# Nuio_Left_Keyboard_Rev_H_UI.net
KiCad netlist of a schematic drawn in Altium Designer
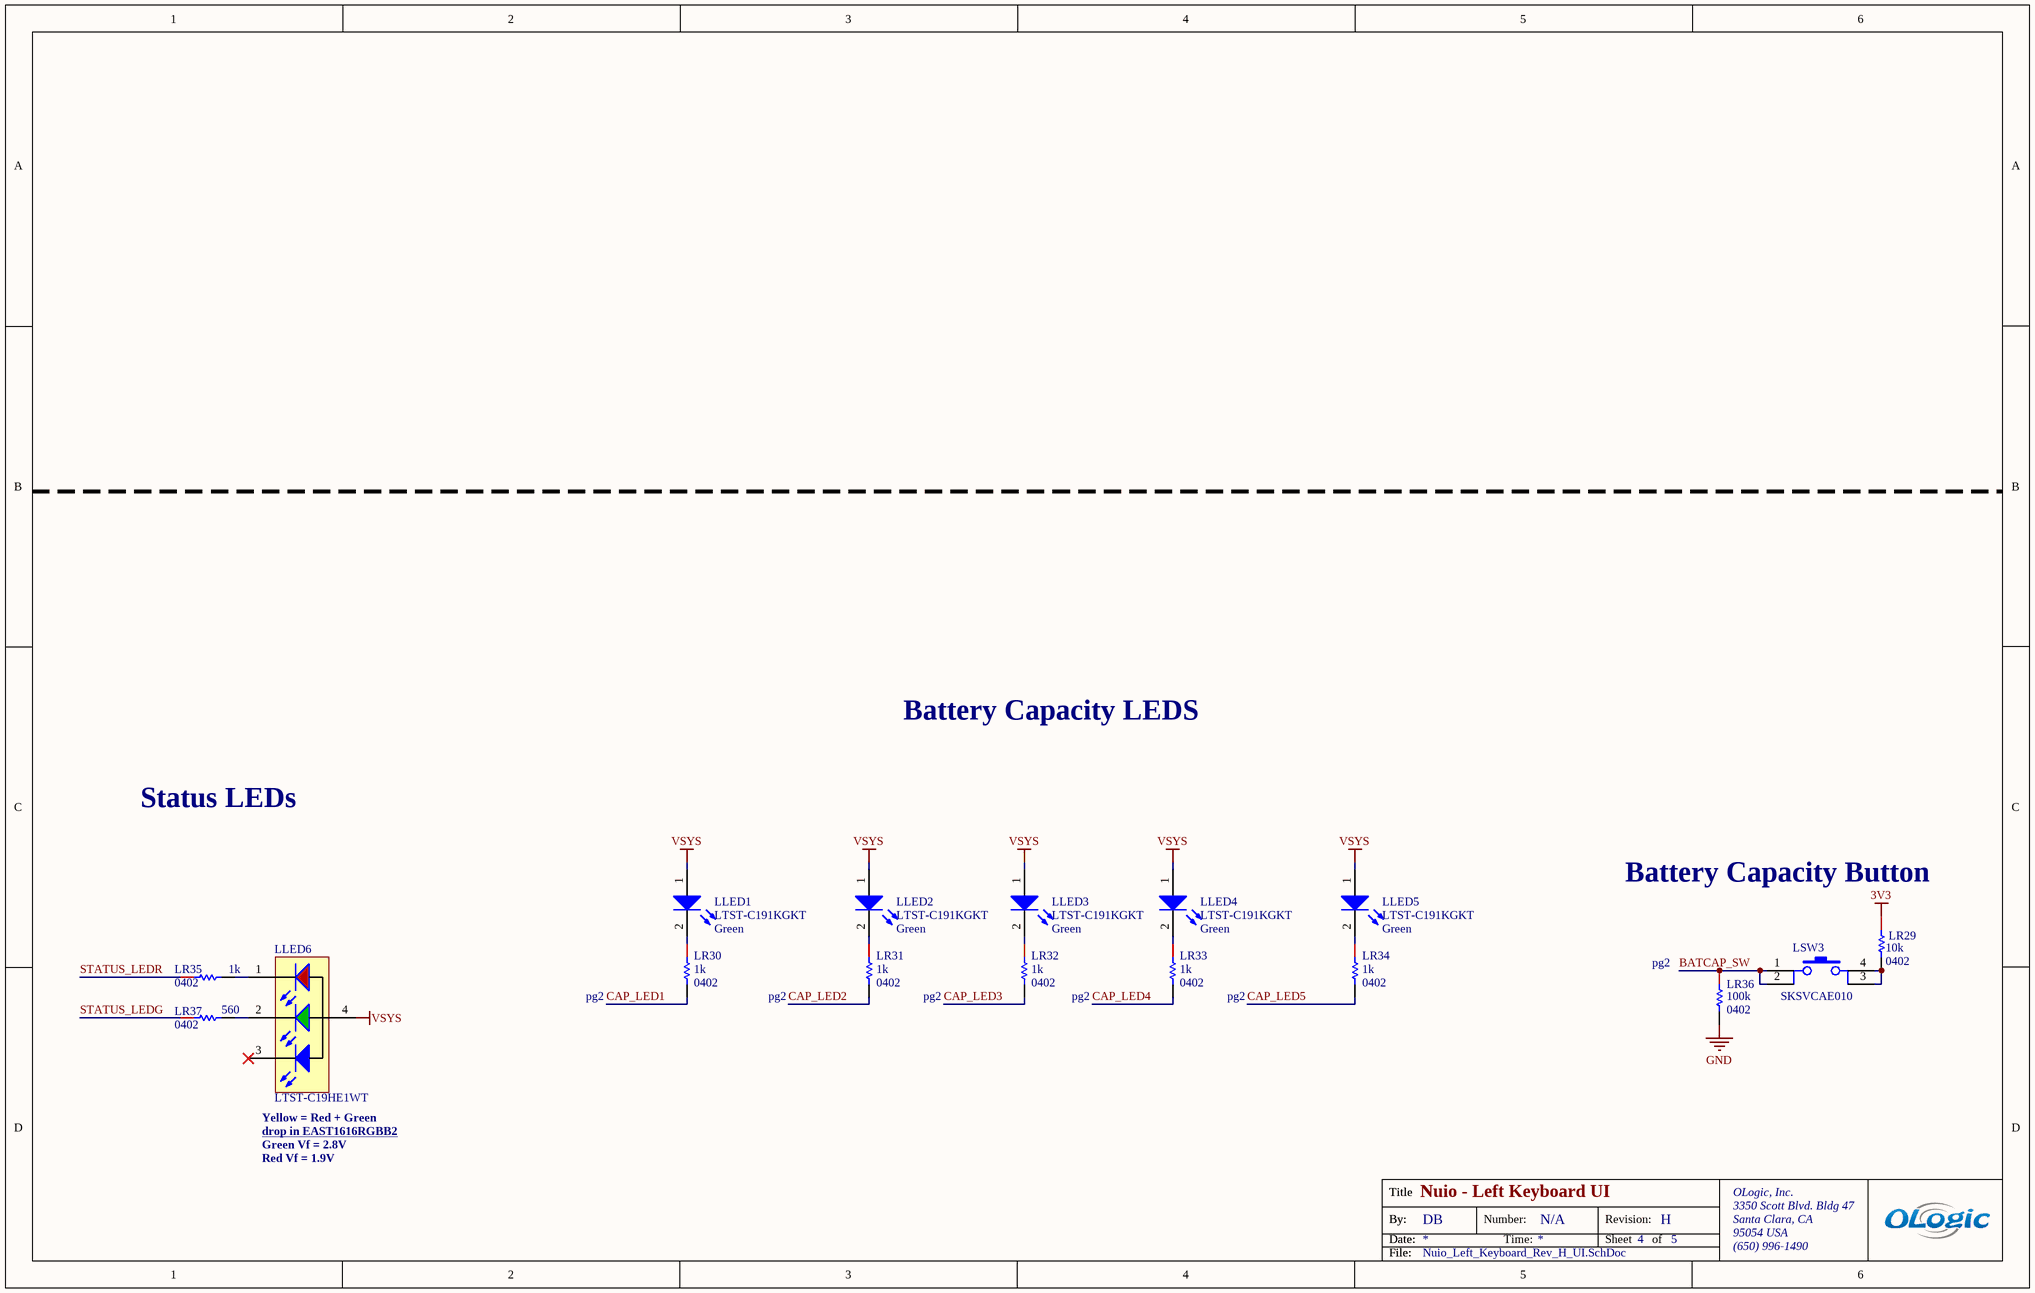
[diagram p0: Nuio_Left_Keyboard_Rev_H_UI.SchDoc]

(export (version "E")
  (design (tool "Eeschema 10.0.6"))
  (components
    (comp (ref "LLED1")
      (value "LTST-C191KGKT")
      (footprint "SM-LED-0603")
      (description "LED GREEN CLEAR THIN 0603 SMD")
      (fields
        (field (name "MANUFACTURER PART NUMBER") "LTST-C191KGKT")
        (field (name "COLOR") "Green")
        (field (name "MANUFACTURER") "Lite-On Inc")
      )
      (libsource (lib "OLogic Nexus Vault") (part "OL_LED"))
    )
    (comp (ref "LLED2")
      (value "LTST-C191KGKT")
      (footprint "SM-LED-0603")
      (description "LED GREEN CLEAR THIN 0603 SMD")
      (fields
        (field (name "MANUFACTURER PART NUMBER") "LTST-C191KGKT")
        (field (name "COLOR") "Green")
        (field (name "MANUFACTURER") "Lite-On Inc")
      )
      (libsource (lib "OLogic Nexus Vault") (part "OL_LED"))
    )
    (comp (ref "LLED3")
      (value "LTST-C191KGKT")
      (footprint "SM-LED-0603")
      (description "LED GREEN CLEAR THIN 0603 SMD")
      (fields
        (field (name "MANUFACTURER PART NUMBER") "LTST-C191KGKT")
        (field (name "COLOR") "Green")
        (field (name "MANUFACTURER") "Lite-On Inc")
      )
      (libsource (lib "OLogic Nexus Vault") (part "OL_LED"))
    )
    (comp (ref "LLED4")
      (value "LTST-C191KGKT")
      (footprint "SM-LED-0603")
      (description "LED GREEN CLEAR THIN 0603 SMD")
      (fields
        (field (name "MANUFACTURER PART NUMBER") "LTST-C191KGKT")
        (field (name "COLOR") "Green")
        (field (name "MANUFACTURER") "Lite-On Inc")
      )
      (libsource (lib "OLogic Nexus Vault") (part "OL_LED"))
    )
    (comp (ref "LLED5")
      (value "LTST-C191KGKT")
      (footprint "SM-LED-0603")
      (description "LED GREEN CLEAR THIN 0603 SMD")
      (fields
        (field (name "MANUFACTURER PART NUMBER") "LTST-C191KGKT")
        (field (name "COLOR") "Green")
        (field (name "MANUFACTURER") "Lite-On Inc")
      )
      (libsource (lib "OLogic Nexus Vault") (part "OL_LED"))
    )
    (comp (ref "LLED6")
      (value "LTST-C19HE1WT")
      (footprint "LTST-C19HE1WT")
      (description "LED RGB 605/525/470NM DIFF SMD")
      (fields (field (name "MANUFACTURER") "Lite-On Inc."))
      (libsource (lib "OLogic Nexus Vault") (part "LTST-C19HE1WT"))
    )
    (comp (ref "LR29")
      (value "RES SMD 10K OHM 1% 1/16W 0402")
      (footprint "RESC0402_YAGEO")
      (fields
        (field (name "RESISTANCE") "10k")
        (field (name "PACKAGE (IMPERIAL)") "0402")
        (field (name "MANUFACTURER") "Yageo")
        (field (name "TOLERANCE") "1%")
        (field (name "MANUFACTURER PART NUMBER") "AT0402FRE0710KL")
      )
      (libsource (lib "OLogic Nexus Vault") (part "OL_Resistor"))
    )
    (comp (ref "LR30")
      (value "RES SMD 1K OHM 1% 1/16W 0402")
      (footprint "RESC0402(1005)_L")
      (fields
        (field (name "RESISTANCE") "1k")
        (field (name "PACKAGE (IMPERIAL)") "0402")
        (field (name "POWER") "63mW")
        (field (name "MANUFACTURER") "Yageo")
        (field (name "TOLERANCE") "1%")
      )
      (libsource (lib "OLogic Nexus Vault") (part "OL_Resistor"))
    )
    (comp (ref "LR31")
      (value "RES SMD 1K OHM 1% 1/16W 0402")
      (footprint "RESC0402(1005)_L")
      (fields
        (field (name "RESISTANCE") "1k")
        (field (name "PACKAGE (IMPERIAL)") "0402")
        (field (name "POWER") "63mW")
        (field (name "MANUFACTURER") "Yageo")
        (field (name "TOLERANCE") "1%")
      )
      (libsource (lib "OLogic Nexus Vault") (part "OL_Resistor"))
    )
    (comp (ref "LR32")
      (value "RES SMD 1K OHM 1% 1/16W 0402")
      (footprint "RESC0402(1005)_L")
      (fields
        (field (name "RESISTANCE") "1k")
        (field (name "PACKAGE (IMPERIAL)") "0402")
        (field (name "POWER") "63mW")
        (field (name "MANUFACTURER") "Yageo")
        (field (name "TOLERANCE") "1%")
      )
      (libsource (lib "OLogic Nexus Vault") (part "OL_Resistor"))
    )
    (comp (ref "LR33")
      (value "RES SMD 1K OHM 1% 1/16W 0402")
      (footprint "RESC0402(1005)_L")
      (fields
        (field (name "RESISTANCE") "1k")
        (field (name "PACKAGE (IMPERIAL)") "0402")
        (field (name "POWER") "63mW")
        (field (name "MANUFACTURER") "Yageo")
        (field (name "TOLERANCE") "1%")
      )
      (libsource (lib "OLogic Nexus Vault") (part "OL_Resistor"))
    )
    (comp (ref "LR34")
      (value "RES SMD 1K OHM 1% 1/16W 0402")
      (footprint "RESC0402(1005)_L")
      (fields
        (field (name "RESISTANCE") "1k")
        (field (name "PACKAGE (IMPERIAL)") "0402")
        (field (name "POWER") "63mW")
        (field (name "MANUFACTURER") "Yageo")
        (field (name "TOLERANCE") "1%")
      )
      (libsource (lib "OLogic Nexus Vault") (part "OL_Resistor"))
    )
    (comp (ref "LR35")
      (value "RES SMD 1K OHM 1% 1/16W 0402")
      (footprint "RESC0402(1005)_L")
      (fields
        (field (name "RESISTANCE") "1k")
        (field (name "PACKAGE (IMPERIAL)") "0402")
        (field (name "POWER") "63mW")
        (field (name "MANUFACTURER") "Yageo")
        (field (name "TOLERANCE") "1%")
      )
      (libsource (lib "OLogic Nexus Vault") (part "OL_Resistor"))
    )
    (comp (ref "LR36")
      (value "100k")
      (footprint "RESC0402(1005)_L")
      (description "±1% 0.063W, 1/16W Chip Resistor 0402 (1005 Metric) Moisture Resistant Thick Film")
      (fields
        (field (name "CASE CODE (IMPERIAL)") "0402")
        (field (name "TOLERANCE") "1%")
        (field (name "MANUFACTURER") "YAGEO")
      )
      (libsource (lib "OLogic Nexus Vault") (part "=Resistance"))
    )
    (comp (ref "LR37")
      (value "560")
      (footprint "RESC0402(1005)_L")
      (description "RES SMD 560 OHM 1% 1/16W 0402")
      (fields
        (field (name "PACKAGE (IMPERIAL)") "0402")
        (field (name "POWER") "63mW")
        (field (name "RESISTANCE") "560")
        (field (name "TOLERANCE") "1%")
      )
      (libsource (lib "OLogic Nexus Vault") (part "=Resistance"))
    )
    (comp (ref "LSW3")
      (value "SKSVCAE010")
      (footprint "SKSVCAE010")
      (description "2.8x1.9mm Compact Type with Projection Surface Mount SKSV Series Tact Switch")
      (fields (field (name "MANUFACTURER") "Alps Alpine"))
      (libsource (lib "OLogic Nexus Vault") (part "OL_Switch_Tactile_4"))
    )
  )
  (nets
    (net (code "1") (name "/BATCAP_SW") (class "Default")
      (node (ref "LR36") (pin "1") (pinfunction "1_1") (pintype "passive"))
      (node (ref "LSW3") (pin "1") (pinfunction "1_1") (pintype "passive"))
      (node (ref "LSW3") (pin "2") (pinfunction "2_2") (pintype "passive"))
    )
    (net (code "2") (name "/CAP_LED1") (class "Default")
      (node (ref "LR30") (pin "2") (pinfunction "2_2") (pintype "passive"))
    )
    (net (code "3") (name "/CAP_LED2") (class "Default")
      (node (ref "LR31") (pin "2") (pinfunction "2_2") (pintype "passive"))
    )
    (net (code "4") (name "/CAP_LED3") (class "Default")
      (node (ref "LR32") (pin "2") (pinfunction "2_2") (pintype "passive"))
    )
    (net (code "5") (name "/CAP_LED4") (class "Default")
      (node (ref "LR33") (pin "2") (pinfunction "2_2") (pintype "passive"))
    )
    (net (code "6") (name "/CAP_LED5") (class "Default")
      (node (ref "LR34") (pin "2") (pinfunction "2_2") (pintype "passive"))
    )
    (net (code "7") (name "/STATUS_LEDG") (class "Default")
      (node (ref "LR37") (pin "1") (pinfunction "1_1") (pintype "passive"))
    )
    (net (code "8") (name "/STATUS_LEDR") (class "Default")
      (node (ref "LR35") (pin "1") (pinfunction "1_1") (pintype "passive"))
    )
    (net (code "9") (name "3V3") (class "Default")
      (node (ref "LR29") (pin "1") (pinfunction "1_1") (pintype "passive"))
    )
    (net (code "10") (name "GND") (class "Default")
      (node (ref "LR36") (pin "2") (pinfunction "2_2") (pintype "passive"))
    )
    (net (code "11") (name "Net-(LLED1-K)") (class "Default")
      (node (ref "LLED1") (pin "2") (pinfunction "K_2") (pintype "passive"))
      (node (ref "LR30") (pin "1") (pinfunction "1_1") (pintype "passive"))
    )
    (net (code "12") (name "Net-(LLED2-K)") (class "Default")
      (node (ref "LLED2") (pin "2") (pinfunction "K_2") (pintype "passive"))
      (node (ref "LR31") (pin "1") (pinfunction "1_1") (pintype "passive"))
    )
    (net (code "13") (name "Net-(LLED3-K)") (class "Default")
      (node (ref "LLED3") (pin "2") (pinfunction "K_2") (pintype "passive"))
      (node (ref "LR32") (pin "1") (pinfunction "1_1") (pintype "passive"))
    )
    (net (code "14") (name "Net-(LLED4-K)") (class "Default")
      (node (ref "LLED4") (pin "2") (pinfunction "K_2") (pintype "passive"))
      (node (ref "LR33") (pin "1") (pinfunction "1_1") (pintype "passive"))
    )
    (net (code "15") (name "Net-(LLED5-K)") (class "Default")
      (node (ref "LLED5") (pin "2") (pinfunction "K_2") (pintype "passive"))
      (node (ref "LR34") (pin "1") (pinfunction "1_1") (pintype "passive"))
    )
    (net (code "16") (name "Net-(LLED6-G)") (class "Default")
      (node (ref "LLED6") (pin "2") (pinfunction "G_2") (pintype "passive"))
      (node (ref "LR37") (pin "2") (pinfunction "2_2") (pintype "passive"))
    )
    (net (code "17") (name "Net-(LLED6-R)") (class "Default")
      (node (ref "LLED6") (pin "1") (pinfunction "R_1") (pintype "passive"))
      (node (ref "LR35") (pin "2") (pinfunction "2_2") (pintype "passive"))
    )
    (net (code "18") (name "Net-(LR29-Pad2)") (class "Default")
      (node (ref "LR29") (pin "2") (pinfunction "2_2") (pintype "passive"))
      (node (ref "LSW3") (pin "3") (pinfunction "3_3") (pintype "passive"))
      (node (ref "LSW3") (pin "4") (pinfunction "4_4") (pintype "passive"))
    )
    (net (code "19") (name "VSYS") (class "Default")
      (node (ref "LLED1") (pin "1") (pinfunction "A_1") (pintype "passive"))
      (node (ref "LLED2") (pin "1") (pinfunction "A_1") (pintype "passive"))
      (node (ref "LLED3") (pin "1") (pinfunction "A_1") (pintype "passive"))
      (node (ref "LLED4") (pin "1") (pinfunction "A_1") (pintype "passive"))
      (node (ref "LLED5") (pin "1") (pinfunction "A_1") (pintype "passive"))
      (node (ref "LLED6") (pin "4") (pinfunction "Anode_4") (pintype "passive"))
    )
    (net (code "20") (name "unconnected-(LLED6-B-Pad3)") (class "Default")
      (node (ref "LLED6") (pin "3") (pinfunction "B_3") (pintype "passive+no_connect"))
    )
  )
)
